# Simple-Bug-2N2222.net
KiCad netlist of a schematic drawn in EAGLE
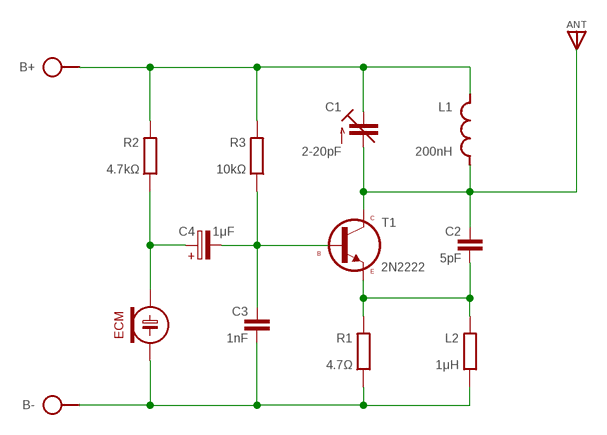
[diagram p0: schematic, sheet 1]

(export (version "E")
  (design (tool "Eeschema 10.0.6"))
  (components
    (comp (ref "ANT")
      (value "ANT")
      (footprint "eagle-import:SPAD")
      (libsource (lib "eagle-import") (part "ANT"))
    )
    (comp (ref "B+")
      (value "HPORT")
      (footprint "eagle-import:SPAD")
      (libsource (lib "eagle-import") (part "HPORT"))
    )
    (comp (ref "B-")
      (value "HPORT")
      (footprint "eagle-import:SPAD")
      (libsource (lib "eagle-import") (part "HPORT"))
    )
    (comp (ref "C1")
      (value "2-20pF")
      (footprint "eagle-import:TRIM-2222-808")
      (libsource (lib "eagle-import") (part "C-TR-PH20127"))
    )
    (comp (ref "C2")
      (value "5pF")
      (footprint "eagle-import:C050-020X036")
      (libsource (lib "eagle-import") (part "C050-020X036"))
    )
    (comp (ref "C3")
      (value "1nF")
      (footprint "eagle-import:C050-020X036")
      (libsource (lib "eagle-import") (part "C050-020X036"))
    )
    (comp (ref "C4")
      (value "1μF")
      (footprint "eagle-import:E2,5-3")
      (libsource (lib "eagle-import") (part "CPOL-HE2,5-3"))
    )
    (comp (ref "ECM")
      (value "ECM-5")
      (footprint "eagle-import:ECM-5")
      (libsource (lib "eagle-import") (part "ECM-5"))
    )
    (comp (ref "L1")
      (value "200nH")
      (footprint "eagle-import:L-04_7V-X")
      (libsource (lib "eagle-import") (part "L-SHORT04/7V-X"))
    )
    (comp (ref "L2")
      (value "1μH")
      (footprint "eagle-import:0204_2V")
      (libsource (lib "eagle-import") (part "R0204/2V-A"))
    )
    (comp (ref "R1")
      (value "4.7Ω")
      (footprint "eagle-import:0204_2V")
      (libsource (lib "eagle-import") (part "R0204/2V-A"))
    )
    (comp (ref "R2")
      (value "4.7kΩ")
      (footprint "eagle-import:0204_10-V")
      (libsource (lib "eagle-import") (part "R0204/10-V"))
    )
    (comp (ref "R3")
      (value "10kΩ")
      (footprint "eagle-import:0204_10-V")
      (libsource (lib "eagle-import") (part "R0204/10-V"))
    )
    (comp (ref "T1")
      (value "2N2222")
      (footprint "eagle-import:TO92")
      (libsource (lib "eagle-import") (part "2N2222"))
    )
  )
  (nets
    (net (code "1") (name "Net-(B+-P$1)") (class "Default")
      (node (ref "B+") (pin "1") (pinfunction "P$1_1") (pintype "passive"))
      (node (ref "C1") (pin "1") (pinfunction "E_1") (pintype "passive"))
      (node (ref "C1") (pin "3") (pinfunction "E_3") (pintype "passive"))
      (node (ref "L1") (pin "2") (pinfunction "2_2") (pintype "passive"))
      (node (ref "R2") (pin "1") (pinfunction "2_1") (pintype "passive"))
      (node (ref "R3") (pin "1") (pinfunction "2_1") (pintype "passive"))
    )
    (net (code "2") (name "Net-(B--P$1)") (class "Default")
      (node (ref "B-") (pin "1") (pinfunction "P$1_1") (pintype "passive"))
      (node (ref "C3") (pin "2") (pinfunction "2_2") (pintype "passive"))
      (node (ref "ECM") (pin "2") (pinfunction "-_2") (pintype "passive"))
      (node (ref "L2") (pin "1") (pinfunction "1_1") (pintype "passive"))
      (node (ref "R1") (pin "1") (pinfunction "1_1") (pintype "passive"))
    )
    (net (code "3") (name "Net-(C1-A)") (class "Default")
      (node (ref "ANT") (pin "1") (pinfunction "1_1") (pintype "output"))
      (node (ref "C1") (pin "2") (pinfunction "A_2") (pintype "passive"))
      (node (ref "C2") (pin "1") (pinfunction "1_1") (pintype "passive"))
      (node (ref "L1") (pin "1") (pinfunction "1_1") (pintype "passive"))
      (node (ref "T1") (pin "3") (pinfunction "C_3") (pintype "passive"))
    )
    (net (code "4") (name "Net-(ECM-+)") (class "Default")
      (node (ref "C4") (pin "+") (pinfunction "+_+") (pintype "passive"))
      (node (ref "ECM") (pin "1") (pinfunction "+_1") (pintype "passive"))
      (node (ref "R2") (pin "2") (pinfunction "1_2") (pintype "passive"))
    )
    (net (code "5") (name "Net-(R3-1)") (class "Default")
      (node (ref "C3") (pin "1") (pinfunction "1_1") (pintype "passive"))
      (node (ref "C4") (pin "-") (pinfunction "-_-") (pintype "passive"))
      (node (ref "R3") (pin "2") (pinfunction "1_2") (pintype "passive"))
      (node (ref "T1") (pin "2") (pinfunction "B_2") (pintype "passive"))
    )
    (net (code "6") (name "Net-(T1-E)") (class "Default")
      (node (ref "C2") (pin "2") (pinfunction "2_2") (pintype "passive"))
      (node (ref "L2") (pin "2") (pinfunction "2_2") (pintype "passive"))
      (node (ref "R1") (pin "2") (pinfunction "2_2") (pintype "passive"))
      (node (ref "T1") (pin "1") (pinfunction "E_1") (pintype "passive"))
    )
  )
)
